# PowerSupply.net
KiCad netlist of a schematic drawn in EAGLE
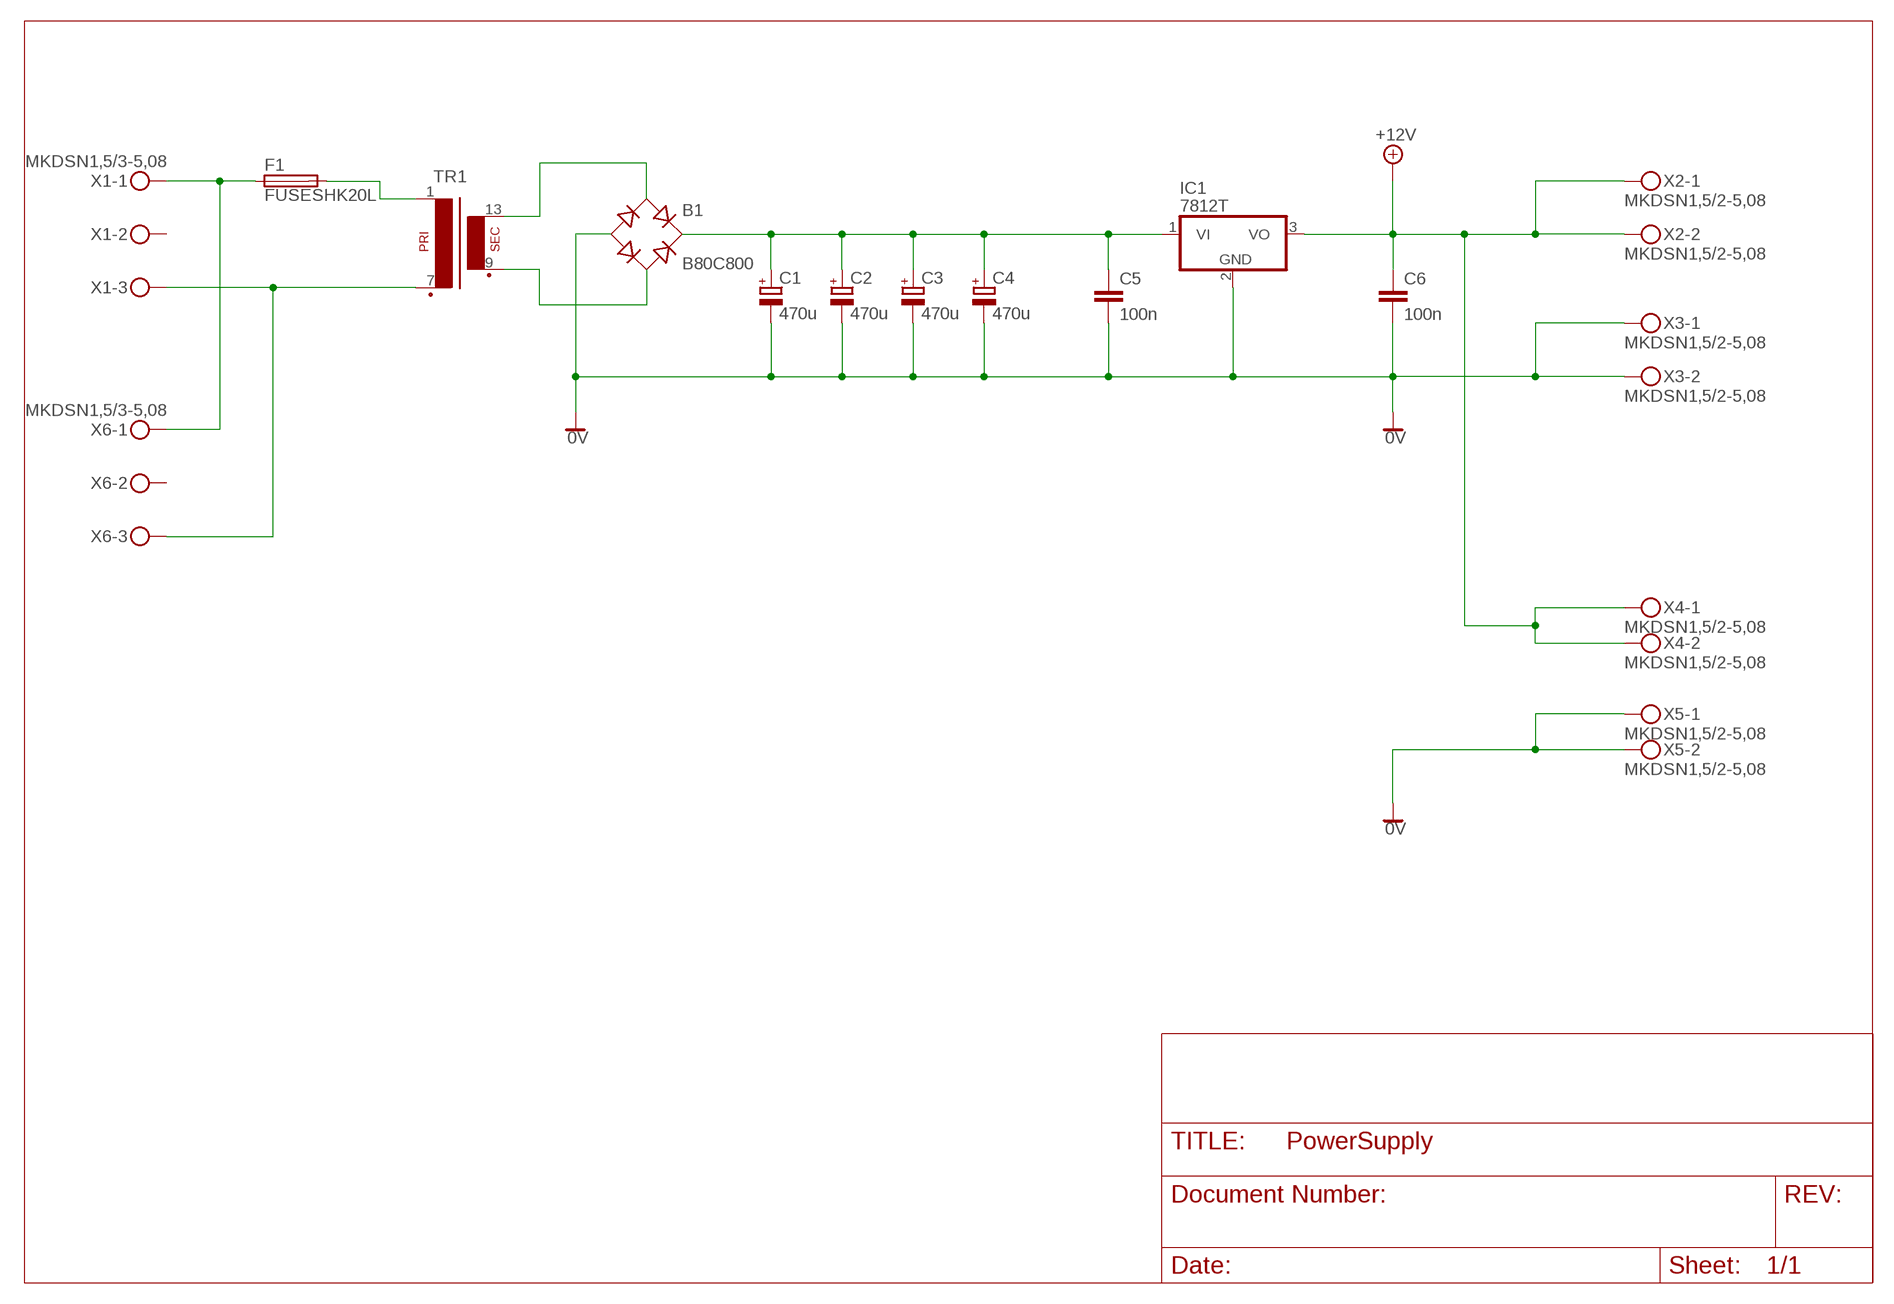
[diagram p0: schematic, sheet 1]

(export (version "E")
  (design (tool "Eeschema 10.0.6"))
  (components
    (comp (ref "B1")
      (value "B80C800")
      (footprint "eagle-import:B-DIL")
      (libsource (lib "eagle-import") (part "B-DIL"))
    )
    (comp (ref "C1")
      (value "470u")
      (footprint "eagle-import:E5-10,5")
      (libsource (lib "eagle-import") (part "CPOL-EUE5-10.5"))
    )
    (comp (ref "C2")
      (value "470u")
      (footprint "eagle-import:E5-10,5")
      (libsource (lib "eagle-import") (part "CPOL-EUE5-10.5"))
    )
    (comp (ref "C3")
      (value "470u")
      (footprint "eagle-import:E5-10,5")
      (libsource (lib "eagle-import") (part "CPOL-EUE5-10.5"))
    )
    (comp (ref "C4")
      (value "470u")
      (footprint "eagle-import:E5-10,5")
      (libsource (lib "eagle-import") (part "CPOL-EUE5-10.5"))
    )
    (comp (ref "C5")
      (value "100n")
      (footprint "eagle-import:C050-024X044")
      (libsource (lib "eagle-import") (part "C-EU050-024X044"))
    )
    (comp (ref "C6")
      (value "100n")
      (footprint "eagle-import:C050-024X044")
      (libsource (lib "eagle-import") (part "C-EU050-024X044"))
    )
    (comp (ref "F1")
      (value "FUSESHK20L")
      (footprint "eagle-import:SHK20L")
      (libsource (lib "eagle-import") (part "FUSESHK20L"))
    )
    (comp (ref "IC1")
      (value "7812T")
      (footprint "eagle-import:TO220H")
      (libsource (lib "eagle-import") (part "78T12"))
    )
    (comp (ref "TR1")
      (value "EI54-1B")
      (footprint "eagle-import:EI54-1B")
      (libsource (lib "eagle-import") (part "EI54-1B"))
    )
    (comp (ref "X1")
      (value "MKDSN1,5/3-5,08")
      (footprint "eagle-import:MKDSN1,5_3-5,08")
      (fields (field (name "MPN") "SMKDSN1,5/3-5,08"))
      (libsource (lib "eagle-import") (part "MKDSN1,5/3-5,08"))
    )
    (comp (ref "X2")
      (value "MKDSN1,5/2-5,08")
      (footprint "eagle-import:MKDSN1,5_2-5,08")
      (fields (field (name "MPN") "MKDSN 1,5/2-5.08"))
      (libsource (lib "eagle-import") (part "MKDSN1,5/2-5,08"))
    )
    (comp (ref "X3")
      (value "MKDSN1,5/2-5,08")
      (footprint "eagle-import:MKDSN1,5_2-5,08")
      (fields (field (name "MPN") "MKDSN 1,5/2-5.08"))
      (libsource (lib "eagle-import") (part "MKDSN1,5/2-5,08"))
    )
    (comp (ref "X4")
      (value "MKDSN1,5/2-5,08")
      (footprint "eagle-import:MKDSN1,5_2-5,08")
      (fields (field (name "MPN") "MKDSN 1,5/2-5.08"))
      (libsource (lib "eagle-import") (part "MKDSN1,5/2-5,08"))
    )
    (comp (ref "X5")
      (value "MKDSN1,5/2-5,08")
      (footprint "eagle-import:MKDSN1,5_2-5,08")
      (fields (field (name "MPN") "MKDSN 1,5/2-5.08"))
      (libsource (lib "eagle-import") (part "MKDSN1,5/2-5,08"))
    )
    (comp (ref "X6")
      (value "MKDSN1,5/3-5,08")
      (footprint "eagle-import:MKDSN1,5_3-5,08")
      (fields
        (field (name "MPN") "SMKDSN1,5/3-5,08")
        (field (name "MPN_1") "SMKDSN1,5/3-5,08")
        (field (name "OC_FARNELL") "1792904")
        (field (name "OC_NEWARK") "70R0299")
      )
      (libsource (lib "eagle-import") (part "MKDSN1,5/3-5,08"))
    )
  )
  (nets
    (net (code "1") (name "+12V") (class "Default")
      (node (ref "C6") (pin "1") (pinfunction "1_1") (pintype "passive"))
      (node (ref "IC1") (pin "3") (pinfunction "VO_3") (pintype "passive"))
      (node (ref "X2") (pin "1") (pinfunction "KL_1") (pintype "passive"))
      (node (ref "X2") (pin "2") (pinfunction "KL_2") (pintype "passive"))
      (node (ref "X4") (pin "1") (pinfunction "KL_1") (pintype "passive"))
      (node (ref "X4") (pin "2") (pinfunction "KL_2") (pintype "passive"))
    )
    (net (code "2") (name "0V") (class "Default")
      (node (ref "B1") (pin "-") (pinfunction "-_-") (pintype "passive"))
      (node (ref "C1") (pin "-") (pinfunction "-_-") (pintype "passive"))
      (node (ref "C2") (pin "-") (pinfunction "-_-") (pintype "passive"))
      (node (ref "C3") (pin "-") (pinfunction "-_-") (pintype "passive"))
      (node (ref "C4") (pin "-") (pinfunction "-_-") (pintype "passive"))
      (node (ref "C5") (pin "2") (pinfunction "2_2") (pintype "passive"))
      (node (ref "C6") (pin "2") (pinfunction "2_2") (pintype "passive"))
      (node (ref "IC1") (pin "2") (pinfunction "GND_2") (pintype "passive"))
      (node (ref "X3") (pin "1") (pinfunction "KL_1") (pintype "passive"))
      (node (ref "X3") (pin "2") (pinfunction "KL_2") (pintype "passive"))
      (node (ref "X5") (pin "1") (pinfunction "KL_1") (pintype "passive"))
      (node (ref "X5") (pin "2") (pinfunction "KL_2") (pintype "passive"))
    )
    (net (code "3") (name "Net-(F1-1)") (class "Default")
      (node (ref "F1") (pin "1A") (pinfunction "1_1A") (pintype "passive"))
      (node (ref "X1") (pin "1") (pinfunction "KL_1") (pintype "passive"))
      (node (ref "X6") (pin "1") (pinfunction "KL_1") (pintype "passive"))
    )
    (net (code "4") (name "Net-(F1-2)") (class "Default")
      (node (ref "F1") (pin "2A") (pinfunction "2_2A") (pintype "passive"))
      (node (ref "TR1") (pin "1") (pinfunction "P1_1") (pintype "passive"))
    )
    (net (code "5") (name "Net-(IC1-VI)") (class "Default")
      (node (ref "B1") (pin "+") (pinfunction "+_+") (pintype "passive"))
      (node (ref "C1") (pin "+") (pinfunction "+_+") (pintype "passive"))
      (node (ref "C2") (pin "+") (pinfunction "+_+") (pintype "passive"))
      (node (ref "C3") (pin "+") (pinfunction "+_+") (pintype "passive"))
      (node (ref "C4") (pin "+") (pinfunction "+_+") (pintype "passive"))
      (node (ref "C5") (pin "1") (pinfunction "1_1") (pintype "passive"))
      (node (ref "IC1") (pin "1") (pinfunction "VI_1") (pintype "input"))
    )
    (net (code "6") (name "Net-(TR1-P2)") (class "Default")
      (node (ref "TR1") (pin "7") (pinfunction "P2_7") (pintype "passive"))
      (node (ref "X1") (pin "3") (pinfunction "KL_3") (pintype "passive"))
      (node (ref "X6") (pin "3") (pinfunction "KL_3") (pintype "passive"))
    )
    (net (code "7") (name "Net-(TR1-S3)") (class "Default")
      (node (ref "B1") (pin "AC2") (pinfunction "AC2_AC2") (pintype "passive"))
      (node (ref "TR1") (pin "9") (pinfunction "S3_9") (pintype "passive"))
    )
    (net (code "8") (name "Net-(TR1-S4)") (class "Default")
      (node (ref "B1") (pin "AC1") (pinfunction "AC1_AC1") (pintype "passive"))
      (node (ref "TR1") (pin "13") (pinfunction "S4_13") (pintype "passive"))
    )
    (net (code "9") (name "unconnected-(X1B-KL-Pad2)") (class "Default")
      (node (ref "X1") (pin "2") (pinfunction "KL_2") (pintype "passive"))
    )
    (net (code "10") (name "unconnected-(X6B-KL-Pad2)") (class "Default")
      (node (ref "X6") (pin "2") (pinfunction "KL_2") (pintype "passive"))
    )
  )
)
